# power_regulator.net
KiCad netlist of a schematic drawn in EAGLE
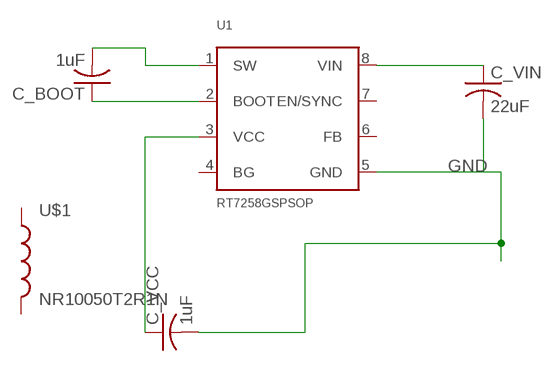
[diagram p0: schematic, sheet 1]

(export (version "E")
  (design (tool "Eeschema 10.0.6"))
  (components
    (comp (ref "C_BOOT")
      (value "1uF")
      (footprint "eagle-import:C0603")
      (libsource (lib "eagle-import") (part "C-USC0603"))
    )
    (comp (ref "C_VCC")
      (value "1uF")
      (footprint "eagle-import:C0603")
      (libsource (lib "eagle-import") (part "C-USC0603"))
    )
    (comp (ref "C_VIN")
      (value "22uF")
      (footprint "eagle-import:C0603")
      (libsource (lib "eagle-import") (part "C-USC0603"))
    )
    (comp (ref "U$1")
      (value "NR10050T2R1N")
      (footprint "eagle-import:NR10050T2R1N")
      (libsource (lib "eagle-import") (part "NR10050T2R1N"))
    )
    (comp (ref "U1")
      (value "RT7258GSPSOP")
      (footprint "eagle-import:SOP08")
      (libsource (lib "eagle-import") (part "RT7258GSPSOP"))
    )
  )
  (nets
    (net (code "1") (name "/GND") (class "Default")
      (node (ref "C_VCC") (pin "2") (pinfunction "2_2") (pintype "passive"))
      (node (ref "C_VIN") (pin "2") (pinfunction "2_2") (pintype "passive"))
      (node (ref "U1") (pin "5") (pinfunction "GND_5") (pintype "bidirectional"))
    )
    (net (code "2") (name "Net-(U1-BOOT)") (class "Default")
      (node (ref "C_BOOT") (pin "1") (pinfunction "1_1") (pintype "passive"))
      (node (ref "U1") (pin "2") (pinfunction "BOOT_2") (pintype "bidirectional"))
    )
    (net (code "3") (name "Net-(U1-SW)") (class "Default")
      (node (ref "C_BOOT") (pin "2") (pinfunction "2_2") (pintype "passive"))
      (node (ref "U1") (pin "1") (pinfunction "SW_1") (pintype "output"))
    )
    (net (code "4") (name "Net-(U1-VCC)") (class "Default")
      (node (ref "C_VCC") (pin "1") (pinfunction "1_1") (pintype "passive"))
      (node (ref "U1") (pin "3") (pinfunction "VCC_3") (pintype "bidirectional"))
    )
    (net (code "5") (name "Net-(U1-VIN)") (class "Default")
      (node (ref "C_VIN") (pin "1") (pinfunction "1_1") (pintype "passive"))
      (node (ref "U1") (pin "8") (pinfunction "VIN_8") (pintype "input"))
    )
    (net (code "6") (name "unconnected-(U$1-1-PadP$1)") (class "Default")
      (node (ref "U$1") (pin "P$1") (pinfunction "1_P$1") (pintype "passive"))
    )
    (net (code "7") (name "unconnected-(U$1-2-PadP$2)") (class "Default")
      (node (ref "U$1") (pin "P$2") (pinfunction "2_P$2") (pintype "passive"))
    )
    (net (code "8") (name "unconnected-(U1-BG-Pad4)") (class "Default")
      (node (ref "U1") (pin "4") (pinfunction "BG_4") (pintype "bidirectional"))
    )
    (net (code "9") (name "unconnected-(U1-EN{slash}SYNC-Pad7)") (class "Default")
      (node (ref "U1") (pin "7") (pinfunction "EN/SYNC_7") (pintype "bidirectional"))
    )
    (net (code "10") (name "unconnected-(U1-FB-Pad6)") (class "Default")
      (node (ref "U1") (pin "6") (pinfunction "FB_6") (pintype "bidirectional"))
    )
  )
)
